# Motor-Y.net
KiCad netlist of a schematic drawn in Altium Designer
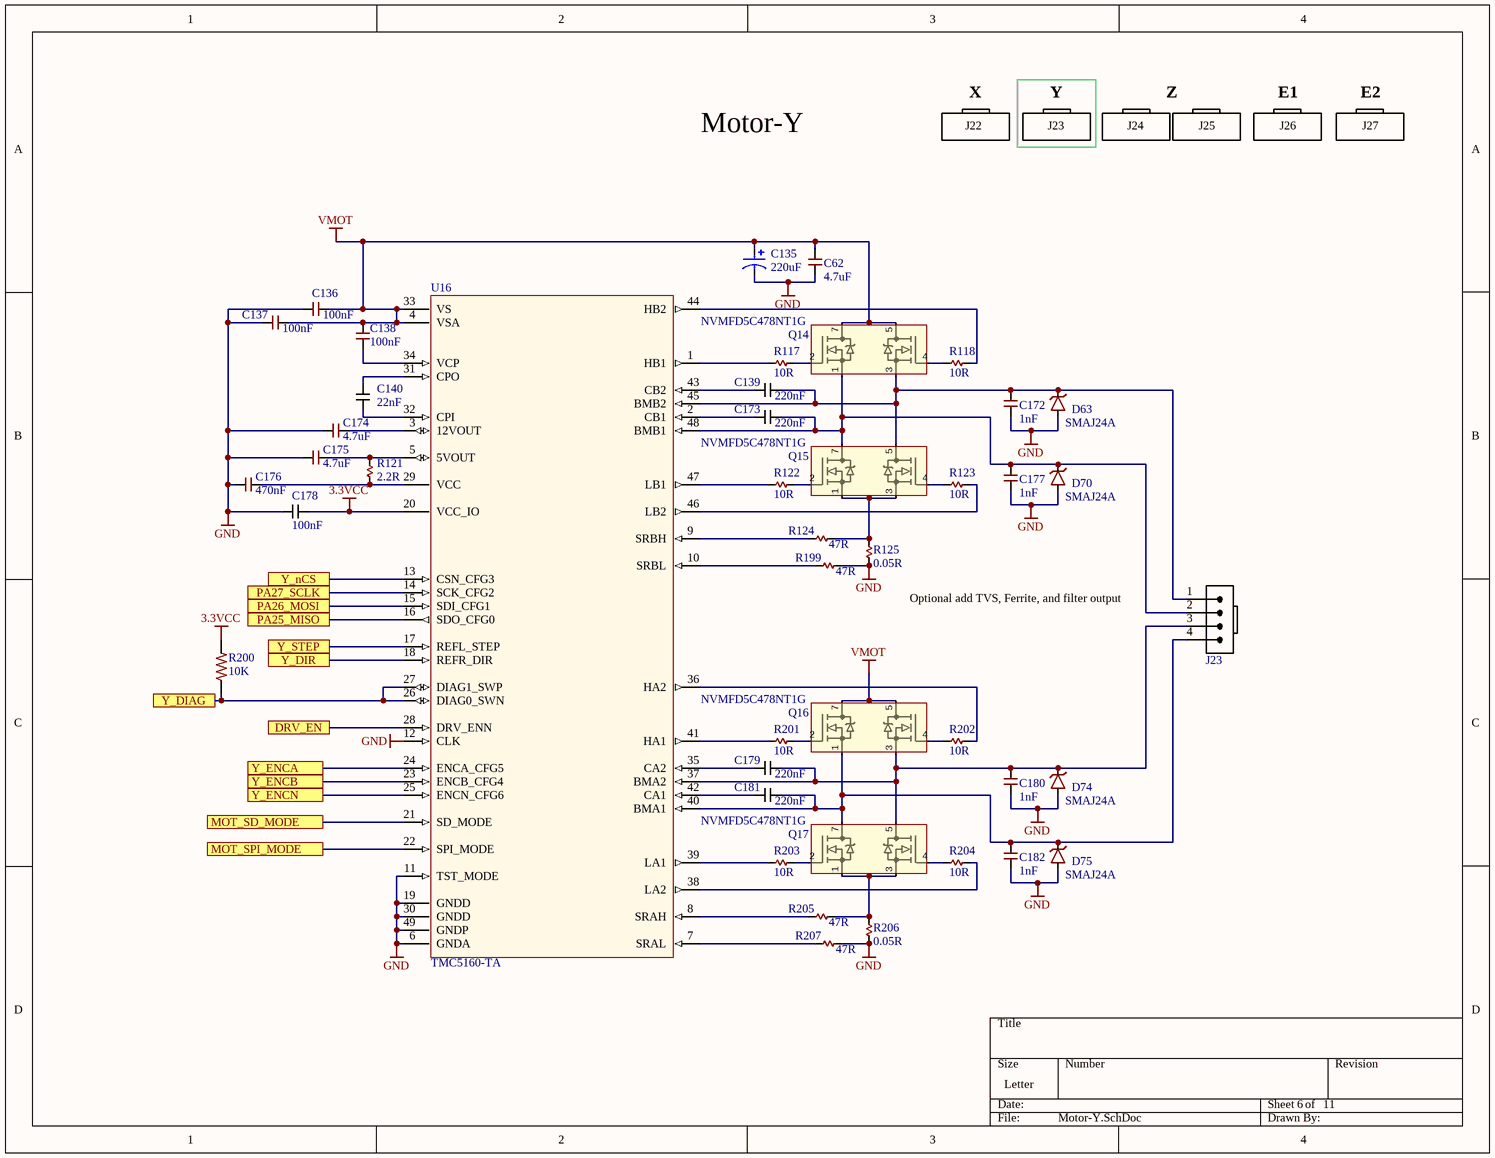
[diagram p0: Motor-Y.SchDoc]

(export (version "E")
  (design (tool "Eeschema 10.0.6"))
  (components
    (comp (ref "C62")
      (value "4.7uF")
      (footprint "C1206")
      (description "CAP CER 1206 4.7uF 50V 10% X5R")
      (fields (field (name "MANUFACTURER") "Kemet") (field (name "PART") "4.7uF 50V X5R 1206"))
      (libsource (lib "Capacitors") (part "4.7uF 1206 50V X5R"))
    )
    (comp (ref "C135")
      (value "220uF")
      (footprint "CAP10X10")
      (description "CAP ALUM 220UF 20% 50V SMD")
      (fields (field (name "MANUFACTURER") "Nichicon") (field (name "TOLERANCE") "20%"))
      (libsource (lib "Capacitors") (part "220uF Al-El 50V"))
    )
    (comp (ref "C136")
      (value "100nF")
      (footprint "C0603")
      (description "CAP CER 0603 100nF 50V 10% X7R")
      (fields (field (name "MANUFACTURER") "Kemet") (field (name "PART") "100nF 50V X7R 0603"))
      (libsource (lib "Capacitors") (part "100nF 0603 50V X7R"))
    )
    (comp (ref "C137")
      (value "100nF")
      (footprint "C0603")
      (description "CAP CER 0603 100nF 50V 10% X7R")
      (fields (field (name "MANUFACTURER") "Kemet") (field (name "PART") "100nF 50V X7R 0603"))
      (libsource (lib "Capacitors") (part "100nF 0603 50V X7R"))
    )
    (comp (ref "C138")
      (value "100nF")
      (footprint "C0603")
      (description "CAP CER 0603 100nF 50V 10% X7R")
      (fields (field (name "MANUFACTURER") "Kemet") (field (name "PART") "100nF 50V X7R 0603"))
      (libsource (lib "Capacitors") (part "100nF 0603 50V X7R"))
    )
    (comp (ref "C139")
      (value "220nF")
      (footprint "C0603")
      (description "CAP CER 0.22UF 50V X7R 0603")
      (fields (field (name "MANUFACTURER") "TDK"))
      (libsource (lib "Capacitors") (part "220nF 50V X7R 0603"))
    )
    (comp (ref "C140")
      (value "22nF")
      (footprint "C0603")
      (description "CAP CER 0.022UF 100V X7R 0603")
      (fields (field (name "MANUFACTURER") "Kemet"))
      (libsource (lib "Capacitors") (part "22nF 100V X7R 0603"))
    )
    (comp (ref "C172")
      (value "1nF")
      (footprint "C0603")
      (description "CAP CER 0603  1nF 50v 10% X7R")
      (fields (field (name "MANUFACTURER") "Kemet") (field (name "TOLERANCE") "+/- 10%"))
      (libsource (lib "Capacitors") (part "1nF 50V X7R 0603"))
    )
    (comp (ref "C173")
      (value "220nF")
      (footprint "C0603")
      (description "CAP CER 0.22UF 50V X7R 0603")
      (fields (field (name "MANUFACTURER") "TDK"))
      (libsource (lib "Capacitors") (part "220nF 50V X7R 0603"))
    )
    (comp (ref "C174")
      (value "4.7uF")
      (footprint "C1206")
      (description "CAP CER 1206 4.7uF 50V 10% X5R")
      (fields (field (name "MANUFACTURER") "Kemet") (field (name "PART") "4.7uF 50V X5R 1206"))
      (libsource (lib "Capacitors") (part "4.7uF 1206 50V X5R"))
    )
    (comp (ref "C175")
      (value "4.7uF")
      (footprint "C0603")
      (description "CAP CER 4.7UF 6.3V X7R 0603")
      (fields (field (name "MANUFACTURER") "Samsung") (field (name "TOLERANCE") "10%"))
      (libsource (lib "Capacitors") (part "4.7uF 0603 6.3V X7R"))
    )
    (comp (ref "C176")
      (value "470nF")
      (footprint "3Delight:C0402")
      (description "470nF 6.3v C0402 - GRM155R60J474KE19D")
      (fields (field (name "TOLERANCE") "10%") (field (name "MANUFACTURER") "Murata"))
      (libsource (lib "Capacitors") (part "470nF 0402 6.3V X5R"))
    )
    (comp (ref "C177")
      (value "1nF")
      (footprint "C0603")
      (description "CAP CER 0603  1nF 50v 10% X7R")
      (fields (field (name "MANUFACTURER") "Kemet") (field (name "TOLERANCE") "+/- 10%"))
      (libsource (lib "Capacitors") (part "1nF 50V X7R 0603"))
    )
    (comp (ref "C178")
      (value "100nF")
      (footprint "C0201 Large Pads")
      (description "CAP CER 0.1UF 6.3V 10% X5R 0201")
      (fields (field (name "MANUFACTURER") "Samsung") (field (name "TOLERANCE") "10%"))
      (libsource (lib "Capacitors") (part "100nF 6.3V X5R 0201"))
    )
    (comp (ref "C179")
      (value "220nF")
      (footprint "C0603")
      (description "CAP CER 0.22UF 50V X7R 0603")
      (fields (field (name "MANUFACTURER") "TDK"))
      (libsource (lib "Capacitors") (part "220nF 50V X7R 0603"))
    )
    (comp (ref "C180")
      (value "1nF")
      (footprint "C0603")
      (description "CAP CER 0603  1nF 50v 10% X7R")
      (fields (field (name "MANUFACTURER") "Kemet") (field (name "TOLERANCE") "+/- 10%"))
      (libsource (lib "Capacitors") (part "1nF 50V X7R 0603"))
    )
    (comp (ref "C181")
      (value "220nF")
      (footprint "C0603")
      (description "CAP CER 0.22UF 50V X7R 0603")
      (fields (field (name "MANUFACTURER") "TDK"))
      (libsource (lib "Capacitors") (part "220nF 50V X7R 0603"))
    )
    (comp (ref "C182")
      (value "1nF")
      (footprint "C0603")
      (description "CAP CER 0603  1nF 50v 10% X7R")
      (fields (field (name "MANUFACTURER") "Kemet") (field (name "TOLERANCE") "+/- 10%"))
      (libsource (lib "Capacitors") (part "1nF 50V X7R 0603"))
    )
    (comp (ref "D63")
      (value "SMAJ24A")
      (footprint "SMA-SM")
      (description "TVS DIODE 24V 38.9V SMA")
      (fields (field (name "MANUFACTURER") "Bourns Inc"))
      (libsource (lib "Diodes") (part "SMAJ24A"))
    )
    (comp (ref "D70")
      (value "SMAJ24A")
      (footprint "SMA-SM")
      (description "TVS DIODE 24V 38.9V SMA")
      (fields (field (name "MANUFACTURER") "Bourns Inc"))
      (libsource (lib "Diodes") (part "SMAJ24A"))
    )
    (comp (ref "D74")
      (value "SMAJ24A")
      (footprint "SMA-SM")
      (description "TVS DIODE 24V 38.9V SMA")
      (fields (field (name "MANUFACTURER") "Bourns Inc"))
      (libsource (lib "Diodes") (part "SMAJ24A"))
    )
    (comp (ref "D75")
      (value "SMAJ24A")
      (footprint "SMA-SM")
      (description "TVS DIODE 24V 38.9V SMA")
      (fields (field (name "MANUFACTURER") "Bourns Inc"))
      (libsource (lib "Diodes") (part "SMAJ24A"))
    )
    (comp (ref "J23")
      (value "Molex 0705430003")
      (footprint "4POL254 PIN-IN-PASTE")
      (description "Molex 4 Pin Clip Connector - Pin In Paste footprint")
      (libsource (lib "Connectors") (part "Molex 0705430003 PIP"))
    )
    (comp (ref "Q14")
      (value "NVMFD5C478NT1G")
      (footprint "SO8FL-Dual (DFN8 5x6, 1.26P Dual Flag)")
      (description "40V 17 MOHM T6 S08FL DUAL")
      (fields (field (name "MANUFACTURER") "ON Semiconductor") (field (name "TOLERANCE") "-NA-"))
      (libsource (lib "Transistors") (part "NVMFD5C478NT1G"))
    )
    (comp (ref "Q15")
      (value "NVMFD5C478NT1G")
      (footprint "SO8FL-Dual (DFN8 5x6, 1.26P Dual Flag)")
      (description "40V 17 MOHM T6 S08FL DUAL")
      (fields (field (name "MANUFACTURER") "ON Semiconductor") (field (name "TOLERANCE") "-NA-"))
      (libsource (lib "Transistors") (part "NVMFD5C478NT1G"))
    )
    (comp (ref "Q16")
      (value "NVMFD5C478NT1G")
      (footprint "SO8FL-Dual (DFN8 5x6, 1.26P Dual Flag)")
      (description "40V 17 MOHM T6 S08FL DUAL")
      (fields (field (name "MANUFACTURER") "ON Semiconductor") (field (name "TOLERANCE") "-NA-"))
      (libsource (lib "Transistors") (part "NVMFD5C478NT1G"))
    )
    (comp (ref "Q17")
      (value "NVMFD5C478NT1G")
      (footprint "SO8FL-Dual (DFN8 5x6, 1.26P Dual Flag)")
      (description "40V 17 MOHM T6 S08FL DUAL")
      (fields (field (name "MANUFACTURER") "ON Semiconductor") (field (name "TOLERANCE") "-NA-"))
      (libsource (lib "Transistors") (part "NVMFD5C478NT1G"))
    )
    (comp (ref "R117")
      (value "10R")
      (footprint "R0402")
      (description "RES SMD 10 OHM 1% 1/16W 0402")
      (fields (field (name "MANUFACTURER") "Yageo") (field (name "PART") "10R 1% 0402"))
      (libsource (lib "Resistors") (part "10R 1% 0402"))
    )
    (comp (ref "R118")
      (value "10R")
      (footprint "R0402")
      (description "RES SMD 10 OHM 1% 1/16W 0402")
      (fields (field (name "MANUFACTURER") "Yageo") (field (name "PART") "10R 1% 0402"))
      (libsource (lib "Resistors") (part "10R 1% 0402"))
    )
    (comp (ref "R121")
      (value "2.2R")
      (footprint "R0402")
      (description "RES SMD 2.2 OHM 5% 1/16W 0402")
      (fields (field (name "MANUFACTURER") "Yageo") (field (name "TOLERANCE") "+/- 5%"))
      (libsource (lib "Resistors") (part "2.2R 5% 0402"))
    )
    (comp (ref "R122")
      (value "10R")
      (footprint "R0402")
      (description "RES SMD 10 OHM 1% 1/16W 0402")
      (fields (field (name "MANUFACTURER") "Yageo") (field (name "PART") "10R 1% 0402"))
      (libsource (lib "Resistors") (part "10R 1% 0402"))
    )
    (comp (ref "R123")
      (value "10R")
      (footprint "R0402")
      (description "RES SMD 10 OHM 1% 1/16W 0402")
      (fields (field (name "MANUFACTURER") "Yageo") (field (name "PART") "10R 1% 0402"))
      (libsource (lib "Resistors") (part "10R 1% 0402"))
    )
    (comp (ref "R124")
      (value "47R")
      (footprint "R0402")
      (description "RES 47 OHM 1% 1/16W 0402")
      (fields (field (name "MANUFACTURER") "Vishay Dale") (field (name "TOLERANCE") "+/- 1%"))
      (libsource (lib "Resistors") (part "47R 1% 0402"))
    )
    (comp (ref "R125")
      (value "0.05R")
      (footprint "R2512")
      (description "RES 0.05 OHM 1% 2W 2512")
      (fields (field (name "MANUFACTURER") "Stackpole") (field (name "TOLERANCE") "+/- 1%"))
      (libsource (lib "Resistors") (part "0.05R 1% 2512"))
    )
    (comp (ref "R199")
      (value "47R")
      (footprint "R0402")
      (description "RES 47 OHM 1% 1/16W 0402")
      (fields (field (name "MANUFACTURER") "Vishay Dale") (field (name "TOLERANCE") "+/- 1%"))
      (libsource (lib "Resistors") (part "47R 1% 0402"))
    )
    (comp (ref "R200")
      (value "10K")
      (footprint "R0402")
      (description "RES SMD 10K OHM 1% 1/16W 0402")
      (fields (field (name "MANUFACTURER") "Yageo") (field (name "PART") "10k 1% 0402"))
      (libsource (lib "3Delight") (part "RC0402FR-0710KP"))
    )
    (comp (ref "R201")
      (value "10R")
      (footprint "R0402")
      (description "RES SMD 10 OHM 1% 1/16W 0402")
      (fields (field (name "MANUFACTURER") "Yageo") (field (name "PART") "10R 1% 0402"))
      (libsource (lib "Resistors") (part "10R 1% 0402"))
    )
    (comp (ref "R202")
      (value "10R")
      (footprint "R0402")
      (description "RES SMD 10 OHM 1% 1/16W 0402")
      (fields (field (name "MANUFACTURER") "Yageo") (field (name "PART") "10R 1% 0402"))
      (libsource (lib "Resistors") (part "10R 1% 0402"))
    )
    (comp (ref "R203")
      (value "10R")
      (footprint "R0402")
      (description "RES SMD 10 OHM 1% 1/16W 0402")
      (fields (field (name "MANUFACTURER") "Yageo") (field (name "PART") "10R 1% 0402"))
      (libsource (lib "Resistors") (part "10R 1% 0402"))
    )
    (comp (ref "R204")
      (value "10R")
      (footprint "R0402")
      (description "RES SMD 10 OHM 1% 1/16W 0402")
      (fields (field (name "MANUFACTURER") "Yageo") (field (name "PART") "10R 1% 0402"))
      (libsource (lib "Resistors") (part "10R 1% 0402"))
    )
    (comp (ref "R205")
      (value "47R")
      (footprint "R0402")
      (description "RES 47 OHM 1% 1/16W 0402")
      (fields (field (name "MANUFACTURER") "Vishay Dale") (field (name "TOLERANCE") "+/- 1%"))
      (libsource (lib "Resistors") (part "47R 1% 0402"))
    )
    (comp (ref "R206")
      (value "0.05R")
      (footprint "R2512")
      (description "RES 0.05 OHM 1% 2W 2512")
      (fields (field (name "MANUFACTURER") "Stackpole") (field (name "TOLERANCE") "+/- 1%"))
      (libsource (lib "Resistors") (part "0.05R 1% 2512"))
    )
    (comp (ref "R207")
      (value "47R")
      (footprint "R0402")
      (description "RES 47 OHM 1% 1/16W 0402")
      (fields (field (name "MANUFACTURER") "Vishay Dale") (field (name "TOLERANCE") "+/- 1%"))
      (libsource (lib "Resistors") (part "47R 1% 0402"))
    )
    (comp (ref "U16")
      (value "TMC5160-TA")
      (footprint "TQFP48-EP")
      (description "IC STEPPER MOTOR DVR TQFP48-EP")
      (fields (field (name "MANUFACTURER") "Trinamic"))
      (libsource (lib "ICs-Motor Controller") (part "TMC5160-TA"))
    )
  )
  (nets
    (net (code "1") (name "/DRV_EN") (class "Default")
      (node (ref "U16") (pin "28") (pinfunction "DRV_ENN_28") (pintype "input"))
    )
    (net (code "2") (name "/MOT_SD_MODE") (class "Default")
      (node (ref "U16") (pin "21") (pinfunction "SD_MODE_21") (pintype "input"))
    )
    (net (code "3") (name "/MOT_SPI_MODE") (class "Default")
      (node (ref "U16") (pin "22") (pinfunction "SPI_MODE_22") (pintype "input"))
    )
    (net (code "4") (name "/PA25_MISO") (class "Default")
      (node (ref "U16") (pin "16") (pinfunction "SDO_CFG0_16") (pintype "output"))
    )
    (net (code "5") (name "/PA26_MOSI") (class "Default")
      (node (ref "U16") (pin "15") (pinfunction "SDI_CFG1_15") (pintype "input"))
    )
    (net (code "6") (name "/PA27_SCLK") (class "Default")
      (node (ref "U16") (pin "14") (pinfunction "SCK_CFG2_14") (pintype "input"))
    )
    (net (code "7") (name "/Y_DIAG") (class "Default")
      (node (ref "R200") (pin "1") (pinfunction "1_1") (pintype "passive"))
      (node (ref "U16") (pin "26") (pinfunction "DIAG0_SWN_26") (pintype "bidirectional"))
      (node (ref "U16") (pin "27") (pinfunction "DIAG1_SWP_27") (pintype "bidirectional"))
    )
    (net (code "8") (name "/Y_DIR") (class "Default")
      (node (ref "U16") (pin "18") (pinfunction "REFR_DIR_18") (pintype "input"))
    )
    (net (code "9") (name "/Y_ENCA") (class "Default")
      (node (ref "U16") (pin "24") (pinfunction "ENCA_CFG5_24") (pintype "input"))
    )
    (net (code "10") (name "/Y_ENCB") (class "Default")
      (node (ref "U16") (pin "23") (pinfunction "ENCB_CFG4_23") (pintype "input"))
    )
    (net (code "11") (name "/Y_ENCN") (class "Default")
      (node (ref "U16") (pin "25") (pinfunction "ENCN_CFG6_25") (pintype "input"))
    )
    (net (code "12") (name "/Y_STEP") (class "Default")
      (node (ref "U16") (pin "17") (pinfunction "REFL_STEP_17") (pintype "input"))
    )
    (net (code "13") (name "/Y_nCS") (class "Default")
      (node (ref "U16") (pin "13") (pinfunction "CSN_CFG3_13") (pintype "input"))
    )
    (net (code "14") (name "3.3VCC") (class "Default")
      (node (ref "C178") (pin "2") (pinfunction "2_2") (pintype "passive"))
      (node (ref "R200") (pin "2") (pinfunction "2_2") (pintype "passive"))
      (node (ref "U16") (pin "20") (pinfunction "VCC_IO_20") (pintype "power_in"))
    )
    (net (code "15") (name "GND") (class "Default")
      (node (ref "C135") (pin "2") (pinfunction "2_2") (pintype "passive"))
      (node (ref "C136") (pin "1") (pinfunction "1_1") (pintype "passive"))
      (node (ref "C137") (pin "1") (pinfunction "1_1") (pintype "passive"))
      (node (ref "C172") (pin "1") (pinfunction "1_1") (pintype "passive"))
      (node (ref "C174") (pin "1") (pinfunction "1_1") (pintype "passive"))
      (node (ref "C175") (pin "1") (pinfunction "1_1") (pintype "passive"))
      (node (ref "C176") (pin "1") (pinfunction "1_1") (pintype "passive"))
      (node (ref "C177") (pin "1") (pinfunction "1_1") (pintype "passive"))
      (node (ref "C178") (pin "1") (pinfunction "1_1") (pintype "passive"))
      (node (ref "C180") (pin "1") (pinfunction "1_1") (pintype "passive"))
      (node (ref "C182") (pin "1") (pinfunction "1_1") (pintype "passive"))
      (node (ref "C62") (pin "1") (pinfunction "1_1") (pintype "passive"))
      (node (ref "D63") (pin "A") (pinfunction "A_A") (pintype "passive"))
      (node (ref "D70") (pin "A") (pinfunction "A_A") (pintype "passive"))
      (node (ref "D74") (pin "A") (pinfunction "A_A") (pintype "passive"))
      (node (ref "D75") (pin "A") (pinfunction "A_A") (pintype "passive"))
      (node (ref "R125") (pin "1") (pinfunction "1_1") (pintype "passive"))
      (node (ref "R199") (pin "2") (pinfunction "2_2") (pintype "passive"))
      (node (ref "R206") (pin "1") (pinfunction "1_1") (pintype "passive"))
      (node (ref "R207") (pin "2") (pinfunction "2_2") (pintype "passive"))
      (node (ref "U16") (pin "11") (pinfunction "TST_MODE_11") (pintype "input"))
      (node (ref "U16") (pin "12") (pinfunction "CLK_12") (pintype "input"))
      (node (ref "U16") (pin "19") (pinfunction "GNDD_19") (pintype "power_in"))
      (node (ref "U16") (pin "30") (pinfunction "GNDD_30") (pintype "power_in"))
      (node (ref "U16") (pin "49") (pinfunction "GNDP_49") (pintype "power_in"))
      (node (ref "U16") (pin "6") (pinfunction "GNDA_6") (pintype "power_in"))
    )
    (net (code "16") (name "Net-(Q14-G1)") (class "Default")
      (node (ref "Q14") (pin "4") (pinfunction "G1_4") (pintype "passive"))
      (node (ref "R118") (pin "1") (pinfunction "1_1") (pintype "passive"))
    )
    (net (code "17") (name "Net-(Q14-G2)") (class "Default")
      (node (ref "Q14") (pin "2") (pinfunction "G2_2") (pintype "passive"))
      (node (ref "R117") (pin "2") (pinfunction "2_2") (pintype "passive"))
    )
    (net (code "18") (name "Net-(Q14-S1)") (class "Default")
      (node (ref "C139") (pin "2") (pinfunction "2_2") (pintype "passive"))
      (node (ref "C172") (pin "2") (pinfunction "2_2") (pintype "passive"))
      (node (ref "D63") (pin "K") (pinfunction "K_K") (pintype "passive"))
      (node (ref "J23") (pin "1") (pinfunction "1_1") (pintype "passive"))
      (node (ref "Q14") (pin "3") (pinfunction "S1_3") (pintype "passive"))
      (node (ref "Q15") (pin "5") (pinfunction "D1_5") (pintype "passive"))
      (node (ref "U16") (pin "45") (pinfunction "BMB2_45") (pintype "input"))
    )
    (net (code "19") (name "Net-(Q14-S2)") (class "Default")
      (node (ref "C173") (pin "2") (pinfunction "2_2") (pintype "passive"))
      (node (ref "C177") (pin "2") (pinfunction "2_2") (pintype "passive"))
      (node (ref "D70") (pin "K") (pinfunction "K_K") (pintype "passive"))
      (node (ref "J23") (pin "2") (pinfunction "2_2") (pintype "passive"))
      (node (ref "Q14") (pin "1") (pinfunction "S2_1") (pintype "passive"))
      (node (ref "Q15") (pin "7") (pinfunction "D2_7") (pintype "passive"))
      (node (ref "U16") (pin "48") (pinfunction "BMB1_48") (pintype "input"))
    )
    (net (code "20") (name "Net-(Q15-G1)") (class "Default")
      (node (ref "Q15") (pin "4") (pinfunction "G1_4") (pintype "passive"))
      (node (ref "R123") (pin "1") (pinfunction "1_1") (pintype "passive"))
    )
    (net (code "21") (name "Net-(Q15-G2)") (class "Default")
      (node (ref "Q15") (pin "2") (pinfunction "G2_2") (pintype "passive"))
      (node (ref "R122") (pin "2") (pinfunction "2_2") (pintype "passive"))
    )
    (net (code "22") (name "Net-(Q15-S1)") (class "Default")
      (node (ref "Q15") (pin "1") (pinfunction "S2_1") (pintype "passive"))
      (node (ref "Q15") (pin "3") (pinfunction "S1_3") (pintype "passive"))
      (node (ref "R124") (pin "2") (pinfunction "2_2") (pintype "passive"))
      (node (ref "R125") (pin "2") (pinfunction "2_2") (pintype "passive"))
    )
    (net (code "23") (name "Net-(Q16-G1)") (class "Default")
      (node (ref "Q16") (pin "4") (pinfunction "G1_4") (pintype "passive"))
      (node (ref "R202") (pin "1") (pinfunction "1_1") (pintype "passive"))
    )
    (net (code "24") (name "Net-(Q16-G2)") (class "Default")
      (node (ref "Q16") (pin "2") (pinfunction "G2_2") (pintype "passive"))
      (node (ref "R201") (pin "2") (pinfunction "2_2") (pintype "passive"))
    )
    (net (code "25") (name "Net-(Q16-S1)") (class "Default")
      (node (ref "C179") (pin "2") (pinfunction "2_2") (pintype "passive"))
      (node (ref "C180") (pin "2") (pinfunction "2_2") (pintype "passive"))
      (node (ref "D74") (pin "K") (pinfunction "K_K") (pintype "passive"))
      (node (ref "J23") (pin "3") (pinfunction "3_3") (pintype "passive"))
      (node (ref "Q16") (pin "3") (pinfunction "S1_3") (pintype "passive"))
      (node (ref "Q17") (pin "5") (pinfunction "D1_5") (pintype "passive"))
      (node (ref "U16") (pin "37") (pinfunction "BMA2_37") (pintype "input"))
    )
    (net (code "26") (name "Net-(Q16-S2)") (class "Default")
      (node (ref "C181") (pin "2") (pinfunction "2_2") (pintype "passive"))
      (node (ref "C182") (pin "2") (pinfunction "2_2") (pintype "passive"))
      (node (ref "D75") (pin "K") (pinfunction "K_K") (pintype "passive"))
      (node (ref "J23") (pin "4") (pinfunction "4_4") (pintype "passive"))
      (node (ref "Q16") (pin "1") (pinfunction "S2_1") (pintype "passive"))
      (node (ref "Q17") (pin "7") (pinfunction "D2_7") (pintype "passive"))
      (node (ref "U16") (pin "40") (pinfunction "BMA1_40") (pintype "input"))
    )
    (net (code "27") (name "Net-(Q17-G1)") (class "Default")
      (node (ref "Q17") (pin "4") (pinfunction "G1_4") (pintype "passive"))
      (node (ref "R204") (pin "1") (pinfunction "1_1") (pintype "passive"))
    )
    (net (code "28") (name "Net-(Q17-G2)") (class "Default")
      (node (ref "Q17") (pin "2") (pinfunction "G2_2") (pintype "passive"))
      (node (ref "R203") (pin "2") (pinfunction "2_2") (pintype "passive"))
    )
    (net (code "29") (name "Net-(Q17-S1)") (class "Default")
      (node (ref "Q17") (pin "1") (pinfunction "S2_1") (pintype "passive"))
      (node (ref "Q17") (pin "3") (pinfunction "S1_3") (pintype "passive"))
      (node (ref "R205") (pin "2") (pinfunction "2_2") (pintype "passive"))
      (node (ref "R206") (pin "2") (pinfunction "2_2") (pintype "passive"))
    )
    (net (code "30") (name "Net-(U16-5VOUT)") (class "Default")
      (node (ref "C175") (pin "2") (pinfunction "2_2") (pintype "passive"))
      (node (ref "R121") (pin "2") (pinfunction "2_2") (pintype "passive"))
      (node (ref "U16") (pin "5") (pinfunction "5VOUT_5") (pintype "bidirectional"))
    )
    (net (code "31") (name "Net-(U16-12VOUT)") (class "Default")
      (node (ref "C174") (pin "2") (pinfunction "2_2") (pintype "passive"))
      (node (ref "U16") (pin "3") (pinfunction "12VOUT_3") (pintype "bidirectional"))
    )
    (net (code "32") (name "Net-(U16-CA1)") (class "Default")
      (node (ref "C181") (pin "1") (pinfunction "1_1") (pintype "passive"))
      (node (ref "U16") (pin "42") (pinfunction "CA1_42") (pintype "input"))
    )
    (net (code "33") (name "Net-(U16-CA2)") (class "Default")
      (node (ref "C179") (pin "1") (pinfunction "1_1") (pintype "passive"))
      (node (ref "U16") (pin "35") (pinfunction "CA2_35") (pintype "input"))
    )
    (net (code "34") (name "Net-(U16-CB1)") (class "Default")
      (node (ref "C173") (pin "1") (pinfunction "1_1") (pintype "passive"))
      (node (ref "U16") (pin "2") (pinfunction "CB1_2") (pintype "input"))
    )
    (net (code "35") (name "Net-(U16-CB2)") (class "Default")
      (node (ref "C139") (pin "1") (pinfunction "1_1") (pintype "passive"))
      (node (ref "U16") (pin "43") (pinfunction "CB2_43") (pintype "input"))
    )
    (net (code "36") (name "Net-(U16-CPI)") (class "Default")
      (node (ref "C140") (pin "1") (pinfunction "1_1") (pintype "passive"))
      (node (ref "U16") (pin "32") (pinfunction "CPI_32") (pintype "input"))
    )
    (net (code "37") (name "Net-(U16-CPO)") (class "Default")
      (node (ref "C140") (pin "2") (pinfunction "2_2") (pintype "passive"))
      (node (ref "U16") (pin "31") (pinfunction "CPO_31") (pintype "input"))
    )
    (net (code "38") (name "Net-(U16-HA1)") (class "Default")
      (node (ref "R201") (pin "1") (pinfunction "1_1") (pintype "passive"))
      (node (ref "U16") (pin "41") (pinfunction "HA1_41") (pintype "output"))
    )
    (net (code "39") (name "Net-(U16-HA2)") (class "Default")
      (node (ref "R202") (pin "2") (pinfunction "2_2") (pintype "passive"))
      (node (ref "U16") (pin "36") (pinfunction "HA2_36") (pintype "output"))
    )
    (net (code "40") (name "Net-(U16-HB1)") (class "Default")
      (node (ref "R117") (pin "1") (pinfunction "1_1") (pintype "passive"))
      (node (ref "U16") (pin "1") (pinfunction "HB1_1") (pintype "output"))
    )
    (net (code "41") (name "Net-(U16-HB2)") (class "Default")
      (node (ref "R118") (pin "2") (pinfunction "2_2") (pintype "passive"))
      (node (ref "U16") (pin "44") (pinfunction "HB2_44") (pintype "output"))
    )
    (net (code "42") (name "Net-(U16-LA1)") (class "Default")
      (node (ref "R203") (pin "1") (pinfunction "1_1") (pintype "passive"))
      (node (ref "U16") (pin "39") (pinfunction "LA1_39") (pintype "output"))
    )
    (net (code "43") (name "Net-(U16-LA2)") (class "Default")
      (node (ref "R204") (pin "2") (pinfunction "2_2") (pintype "passive"))
      (node (ref "U16") (pin "38") (pinfunction "LA2_38") (pintype "output"))
    )
    (net (code "44") (name "Net-(U16-LB1)") (class "Default")
      (node (ref "R122") (pin "1") (pinfunction "1_1") (pintype "passive"))
      (node (ref "U16") (pin "47") (pinfunction "LB1_47") (pintype "output"))
    )
    (net (code "45") (name "Net-(U16-LB2)") (class "Default")
      (node (ref "R123") (pin "2") (pinfunction "2_2") (pintype "passive"))
      (node (ref "U16") (pin "46") (pinfunction "LB2_46") (pintype "output"))
    )
    (net (code "46") (name "Net-(U16-SRAH)") (class "Default")
      (node (ref "R205") (pin "1") (pinfunction "1_1") (pintype "passive"))
      (node (ref "U16") (pin "8") (pinfunction "SRAH_8") (pintype "input"))
    )
    (net (code "47") (name "Net-(U16-SRAL)") (class "Default")
      (node (ref "R207") (pin "1") (pinfunction "1_1") (pintype "passive"))
      (node (ref "U16") (pin "7") (pinfunction "SRAL_7") (pintype "input"))
    )
    (net (code "48") (name "Net-(U16-SRBH)") (class "Default")
      (node (ref "R124") (pin "1") (pinfunction "1_1") (pintype "passive"))
      (node (ref "U16") (pin "9") (pinfunction "SRBH_9") (pintype "input"))
    )
    (net (code "49") (name "Net-(U16-SRBL)") (class "Default")
      (node (ref "R199") (pin "1") (pinfunction "1_1") (pintype "passive"))
      (node (ref "U16") (pin "10") (pinfunction "SRBL_10") (pintype "input"))
    )
    (net (code "50") (name "Net-(U16-VCC)") (class "Default")
      (node (ref "C176") (pin "2") (pinfunction "2_2") (pintype "passive"))
      (node (ref "R121") (pin "1") (pinfunction "1_1") (pintype "passive"))
      (node (ref "U16") (pin "29") (pinfunction "VCC_29") (pintype "power_in"))
    )
    (net (code "51") (name "Net-(U16-VCP)") (class "Default")
      (node (ref "C138") (pin "1") (pinfunction "1_1") (pintype "passive"))
      (node (ref "U16") (pin "34") (pinfunction "VCP_34") (pintype "input"))
    )
    (net (code "52") (name "VMOT") (class "Default")
      (node (ref "C135") (pin "1") (pinfunction "1_1") (pintype "passive"))
      (node (ref "C136") (pin "2") (pinfunction "2_2") (pintype "passive"))
      (node (ref "C137") (pin "2") (pinfunction "2_2") (pintype "passive"))
      (node (ref "C138") (pin "2") (pinfunction "2_2") (pintype "passive"))
      (node (ref "C62") (pin "2") (pinfunction "2_2") (pintype "passive"))
      (node (ref "Q14") (pin "5") (pinfunction "D1_5") (pintype "passive"))
      (node (ref "Q14") (pin "7") (pinfunction "D2_7") (pintype "passive"))
      (node (ref "Q16") (pin "5") (pinfunction "D1_5") (pintype "passive"))
      (node (ref "Q16") (pin "7") (pinfunction "D2_7") (pintype "passive"))
      (node (ref "U16") (pin "33") (pinfunction "VS_33") (pintype "power_in"))
      (node (ref "U16") (pin "4") (pinfunction "VSA_4") (pintype "power_in"))
    )
  )
)
